# SS_Power-V3_0_a.net
KiCad netlist of a schematic drawn in Altium Designer
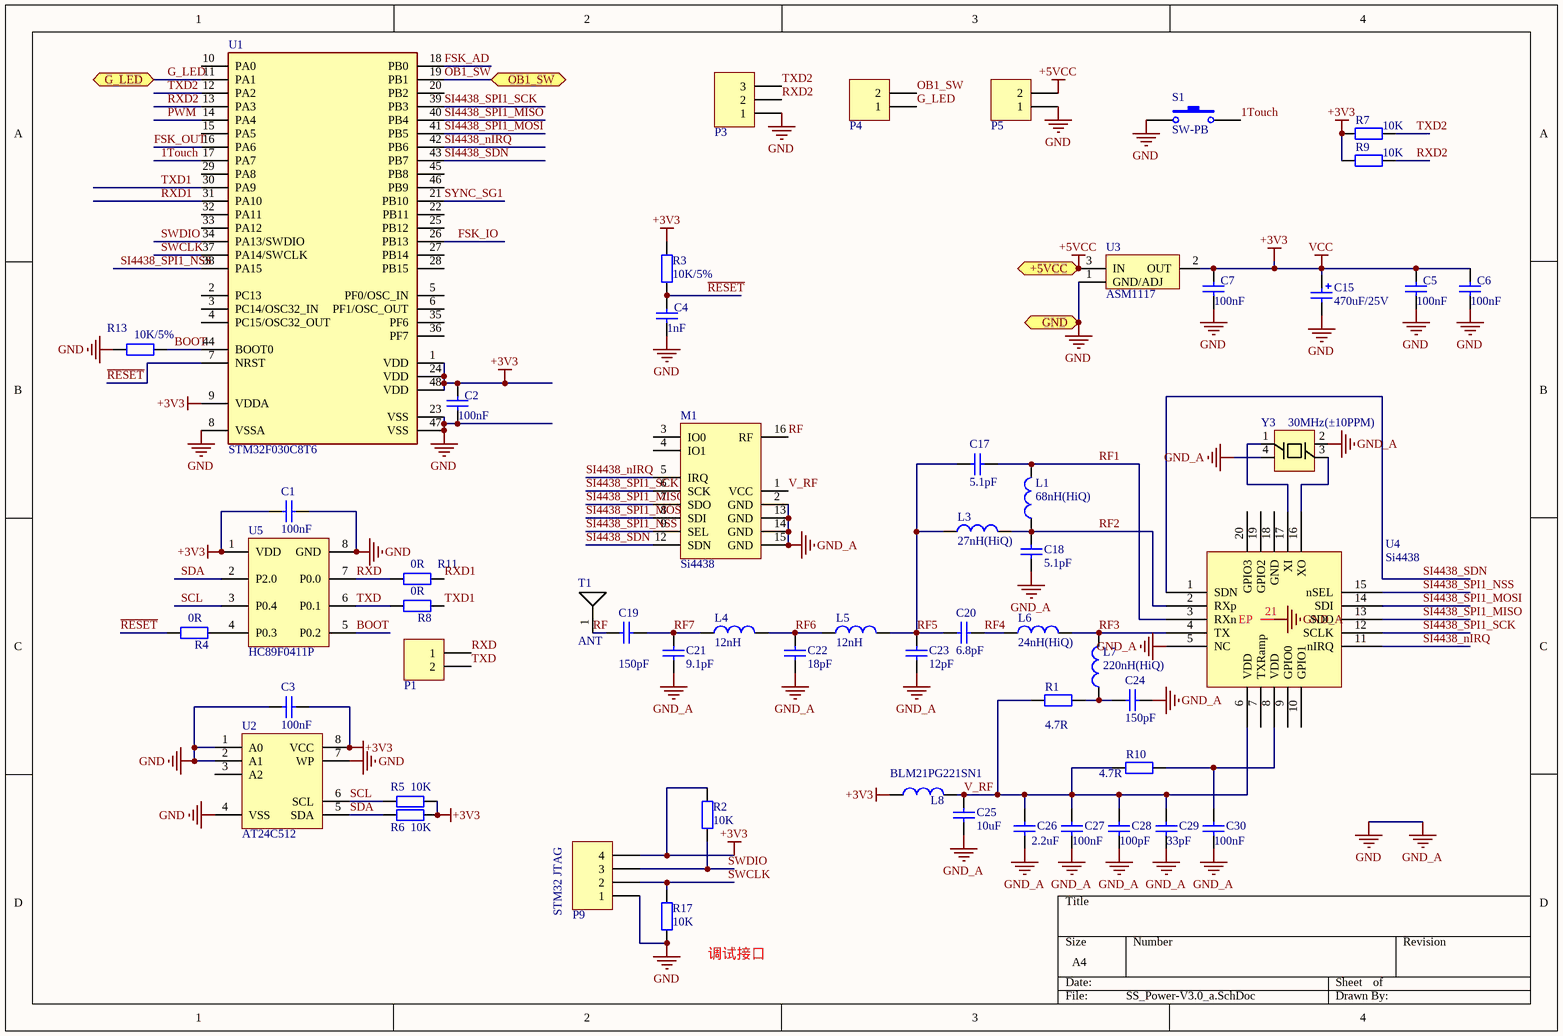
[diagram p0: SS_Power-V3.0_a.SchDoc]

(export (version "E")
  (design (tool "Eeschema 10.0.6"))
  (components
    (comp (ref "C1")
      (value "100nF")
      (footprint "C-RAD-0603")
      (description "无极性电容")
      (fields (field (name "PUBLISHER") "Altium Limited"))
      (libsource (lib "liu_ginny") (part "Cap"))
    )
    (comp (ref "C2")
      (value "100nF")
      (footprint "C-RAD-0603")
      (description "无极性电容")
      (fields (field (name "PUBLISHER") "Altium Limited"))
      (libsource (lib "liu_ginny") (part "Cap"))
    )
    (comp (ref "C3")
      (value "100nF")
      (footprint "C-RAD-0603")
      (description "无极性电容")
      (fields (field (name "PUBLISHER") "Altium Limited"))
      (libsource (lib "liu_ginny") (part "Cap"))
    )
    (comp (ref "C4")
      (value "1nF")
      (footprint "C0402")
      (description "无极性电容")
      (fields (field (name "PUBLISHER") "Altium Limited"))
      (libsource (lib "liu_ginny") (part "Cap"))
    )
    (comp (ref "C5")
      (value "100nF")
      (footprint "C-RAD-0603")
      (description "无极性电容")
      (fields (field (name "PUBLISHER") "Altium Limited"))
      (libsource (lib "liu_ginny") (part "Cap"))
    )
    (comp (ref "C6")
      (value "100nF")
      (footprint "C-RAD-0603")
      (description "无极性电容")
      (fields (field (name "PUBLISHER") "Altium Limited"))
      (libsource (lib "liu_ginny") (part "Cap"))
    )
    (comp (ref "C7")
      (value "100nF")
      (footprint "C-RAD-0603")
      (description "无极性电容")
      (fields (field (name "PUBLISHER") "Altium Limited"))
      (libsource (lib "liu_ginny") (part "Cap"))
    )
    (comp (ref "C15")
      (value "470uF/25V")
      (footprint "C-RB-5/2")
      (description "电解电容")
      (libsource (lib "liu_ginny") (part "CAP3"))
    )
    (comp (ref "C17")
      (value "5.1pF")
      (footprint "C0402")
      (description "无极性电容")
      (fields (field (name "PUBLISHER") "Altium Limited"))
      (libsource (lib "liu_ginny") (part "Cap"))
    )
    (comp (ref "C18")
      (value "5.1pF")
      (footprint "C0402")
      (description "无极性电容")
      (fields (field (name "PUBLISHER") "Altium Limited"))
      (libsource (lib "liu_ginny") (part "Cap"))
    )
    (comp (ref "C19")
      (value "150pF")
      (footprint "C0402")
      (description "无极性电容")
      (fields (field (name "PUBLISHER") "Altium Limited"))
      (libsource (lib "liu_ginny") (part "Cap"))
    )
    (comp (ref "C20")
      (value "6.8pF")
      (footprint "C0402")
      (description "无极性电容")
      (fields (field (name "PUBLISHER") "Altium Limited"))
      (libsource (lib "liu_ginny") (part "Cap"))
    )
    (comp (ref "C21")
      (value "9.1pF")
      (footprint "C0402")
      (description "无极性电容")
      (fields (field (name "PUBLISHER") "Altium Limited"))
      (libsource (lib "liu_ginny") (part "Cap"))
    )
    (comp (ref "C22")
      (value "18pF")
      (footprint "C0402")
      (description "无极性电容")
      (fields (field (name "PUBLISHER") "Altium Limited"))
      (libsource (lib "liu_ginny") (part "Cap"))
    )
    (comp (ref "C23")
      (value "12pF")
      (footprint "C0402")
      (description "无极性电容")
      (fields (field (name "PUBLISHER") "Altium Limited"))
      (libsource (lib "liu_ginny") (part "Cap"))
    )
    (comp (ref "C24")
      (value "150pF")
      (footprint "C0402")
      (description "无极性电容")
      (fields (field (name "PUBLISHER") "Altium Limited"))
      (libsource (lib "liu_ginny") (part "Cap"))
    )
    (comp (ref "C25")
      (value "10uF")
      (footprint "C0603")
      (description "无极性电容")
      (fields (field (name "PUBLISHER") "Altium Limited"))
      (libsource (lib "liu_ginny") (part "Cap"))
    )
    (comp (ref "C26")
      (value "2.2uF")
      (footprint "C0603")
      (description "无极性电容")
      (fields (field (name "PUBLISHER") "Altium Limited"))
      (libsource (lib "liu_ginny") (part "Cap"))
    )
    (comp (ref "C27")
      (value "100nF")
      (footprint "C0402")
      (description "无极性电容")
      (fields (field (name "PUBLISHER") "Altium Limited"))
      (libsource (lib "liu_ginny") (part "Cap"))
    )
    (comp (ref "C28")
      (value "100pF")
      (footprint "C0402")
      (description "无极性电容")
      (fields (field (name "PUBLISHER") "Altium Limited"))
      (libsource (lib "liu_ginny") (part "Cap"))
    )
    (comp (ref "C29")
      (value "33pF")
      (footprint "C0402")
      (description "无极性电容")
      (fields (field (name "PUBLISHER") "Altium Limited"))
      (libsource (lib "liu_ginny") (part "Cap"))
    )
    (comp (ref "C30")
      (value "100nF")
      (footprint "C0402")
      (description "无极性电容")
      (fields (field (name "PUBLISHER") "Altium Limited"))
      (libsource (lib "liu_ginny") (part "Cap"))
    )
    (comp (ref "L1")
      (value "68nH(HiQ)")
      (footprint "0402")
      (description "电感")
      (fields (field (name "PUBLISHER") "Altium Limited"))
      (libsource (lib "liu_ginny") (part "Inductor"))
    )
    (comp (ref "L3")
      (value "27nH(HiQ)")
      (footprint "0402")
      (description "电感")
      (fields (field (name "PUBLISHER") "Altium Limited"))
      (libsource (lib "liu_ginny") (part "Inductor"))
    )
    (comp (ref "L4")
      (value "12nH")
      (footprint "0402")
      (description "电感")
      (fields (field (name "PUBLISHER") "Altium Limited"))
      (libsource (lib "liu_ginny") (part "Inductor"))
    )
    (comp (ref "L5")
      (value "12nH")
      (footprint "0402")
      (description "电感")
      (fields (field (name "PUBLISHER") "Altium Limited"))
      (libsource (lib "liu_ginny") (part "Inductor"))
    )
    (comp (ref "L6")
      (value "24nH(HiQ)")
      (footprint "0402")
      (description "电感")
      (fields (field (name "PUBLISHER") "Altium Limited"))
      (libsource (lib "liu_ginny") (part "Inductor"))
    )
    (comp (ref "L7")
      (value "220nH(HiQ)")
      (footprint "0402")
      (description "电感")
      (fields (field (name "PUBLISHER") "Altium Limited"))
      (libsource (lib "liu_ginny") (part "Inductor"))
    )
    (comp (ref "L8")
      (value "BLM21PG221SN1")
      (footprint "0805-1")
      (description "电感")
      (fields (field (name "PUBLISHER") "Altium Limited"))
      (libsource (lib "liu_ginny") (part "Inductor"))
    )
    (comp (ref "M1")
      (value "Si4438")
      (footprint "HPD01")
      (description "SI4438模块")
      (libsource (lib "liu_ginny") (part "SI4438-HPD07"))
    )
    (comp (ref "P1")
      (value "Header 2")
      (footprint "hdr1.27x2_host")
      (description "接插件")
      (fields (field (name "PUBLISHER") "Altium Limited"))
      (libsource (lib "liu_ginny") (part "Header 2"))
    )
    (comp (ref "P3")
      (value "Header 3")
      (footprint "HDR3X1/1.25")
      (description "接插件")
      (fields (field (name "PUBLISHER") "Altium Limited"))
      (libsource (lib "liu_ginny") (part "Header 3"))
    )
    (comp (ref "P4")
      (value "Header 2")
      (footprint "HDR2X1_2.0")
      (description "接插件")
      (fields (field (name "PUBLISHER") "Altium Limited"))
      (libsource (lib "") (part "Header 2_1"))
    )
    (comp (ref "P5")
      (value "Header 2")
      (footprint "HDR2X1_2.0")
      (description "接插件")
      (fields (field (name "PUBLISHER") "Altium Limited"))
      (libsource (lib "") (part "Header 2_1"))
    )
    (comp (ref "P9")
      (value "Header 4")
      (footprint "HDR4X1/1.25B2M")
      (description "接插件")
      (fields (field (name "PUBLISHER") "Altium Limited"))
      (libsource (lib "liu_ginny") (part "Header 4"))
    )
    (comp (ref "R1")
      (value "4.7R")
      (footprint "R0402")
      (description "电阻")
      (fields (field (name "PUBLISHER") "Altium Limited"))
      (libsource (lib "liu_ginny") (part "Res1"))
    )
    (comp (ref "R2")
      (value "10K")
      (footprint "R0402")
      (description "电阻")
      (fields (field (name "PUBLISHER") "Altium Limited"))
      (libsource (lib "") (part "Res1_1"))
    )
    (comp (ref "R3")
      (value "10K/5%")
      (footprint "R0402")
      (description "电阻")
      (fields (field (name "PUBLISHER") "Altium Limited"))
      (libsource (lib "") (part "Res1_2"))
    )
    (comp (ref "R4")
      (value "0R")
      (footprint "R0402")
      (description "电阻")
      (fields (field (name "PUBLISHER") "Altium Limited"))
      (libsource (lib "liu_ginny") (part "Res1"))
    )
    (comp (ref "R5")
      (value "10K")
      (footprint "R0402")
      (description "电阻")
      (fields (field (name "PUBLISHER") "Altium Limited"))
      (libsource (lib "liu_ginny") (part "Res1"))
    )
    (comp (ref "R6")
      (value "10K")
      (footprint "R0402")
      (description "电阻")
      (fields (field (name "PUBLISHER") "Altium Limited"))
      (libsource (lib "liu_ginny") (part "Res1"))
    )
    (comp (ref "R7")
      (value "10K")
      (footprint "R0402")
      (description "电阻")
      (fields (field (name "PUBLISHER") "Altium Limited"))
      (libsource (lib "liu_ginny") (part "Res1"))
    )
    (comp (ref "R8")
      (value "0R")
      (footprint "R0402")
      (description "电阻")
      (fields (field (name "PUBLISHER") "Altium Limited"))
      (libsource (lib "liu_ginny") (part "Res1"))
    )
    (comp (ref "R9")
      (value "10K")
      (footprint "R0402")
      (description "电阻")
      (fields (field (name "PUBLISHER") "Altium Limited"))
      (libsource (lib "liu_ginny") (part "Res1"))
    )
    (comp (ref "R10")
      (value "4.7R")
      (footprint "R0402")
      (description "电阻")
      (fields (field (name "PUBLISHER") "Altium Limited"))
      (libsource (lib "liu_ginny") (part "Res1"))
    )
    (comp (ref "R11")
      (value "0R")
      (footprint "R0402")
      (description "电阻")
      (fields (field (name "PUBLISHER") "Altium Limited"))
      (libsource (lib "liu_ginny") (part "Res1"))
    )
    (comp (ref "R13")
      (value "10K/5%")
      (footprint "R0402")
      (description "电阻")
      (fields (field (name "PUBLISHER") "Altium Limited"))
      (libsource (lib "liu_ginny") (part "Res1"))
    )
    (comp (ref "R17")
      (value "10K")
      (footprint "R0402")
      (description "电阻")
      (fields (field (name "PUBLISHER") "Altium Limited"))
      (libsource (lib "") (part "Res1_1"))
    )
    (comp (ref "S1")
      (value "SW-PB")
      (footprint "swich_micro")
      (description "微动开关")
      (fields (field (name "PUBLISHER") "Altium Limited"))
      (libsource (lib "liu_ginny") (part "SW-PB"))
    )
    (comp (ref "T1")
      (value "ANT")
      (footprint "ANT470")
      (description "470M弹簧天线")
      (libsource (lib "SCH Library") (part "ANT"))
    )
    (comp (ref "U1")
      (value "STM32F030C8T6")
      (footprint "LQFP48_7X7X05P")
      (description "MCU")
      (libsource (lib "liu_ginny") (part "STM32F030C8T6"))
    )
    (comp (ref "U2")
      (value "AT24C512")
      (footprint "SOIC8_N")
      (description "EEROM存储器")
      (libsource (lib "liu_ginny") (part "AT24C02"))
    )
    (comp (ref "U3") (value "ASM1117") (footprint "SOT-223") (libsource (lib "Core2") (part "ASM1117")))
    (comp (ref "U4")
      (value "Si4438")
      (footprint "QFN20/0.5")
      (description "无线收发器")
      (libsource (lib "liu_ginny") (part "Si4438"))
    )
    (comp (ref "U5")
      (value "HC89F0411P")
      (footprint "SO-8")
      (description "芯圣8脚51单片机")
      (libsource (lib "liu_ginny") (part "HC89F0411P"))
    )
    (comp (ref "Y3")
      (value "30MHz(±10PPM)")
      (footprint "XTAL4/3.2X2.5/S")
      (description "四脚无源")
      (libsource (lib "liu_ginny") (part "XTAL_4"))
    )
  )
  (nets
    (net (code "1") (name "+3V3") (class "Default")
      (node (ref "C1") (pin "2") (pinfunction "2_2") (pintype "passive"))
      (node (ref "C15") (pin "1") (pinfunction "1_1") (pintype "passive"))
      (node (ref "C2") (pin "2") (pinfunction "2_2") (pintype "passive"))
      (node (ref "C3") (pin "1") (pinfunction "1_1") (pintype "passive"))
      (node (ref "C5") (pin "2") (pinfunction "2_2") (pintype "passive"))
      (node (ref "C6") (pin "2") (pinfunction "2_2") (pintype "passive"))
      (node (ref "C7") (pin "2") (pinfunction "2_2") (pintype "passive"))
      (node (ref "L8") (pin "1") (pinfunction "1_1") (pintype "passive"))
      (node (ref "P9") (pin "4") (pinfunction "4_4") (pintype "passive"))
      (node (ref "R2") (pin "1") (pinfunction "1_1") (pintype "passive"))
      (node (ref "R3") (pin "2") (pinfunction "2_2") (pintype "passive"))
      (node (ref "R5") (pin "2") (pinfunction "2_2") (pintype "passive"))
      (node (ref "R6") (pin "2") (pinfunction "2_2") (pintype "passive"))
      (node (ref "R7") (pin "1") (pinfunction "1_1") (pintype "passive"))
      (node (ref "R9") (pin "1") (pinfunction "1_1") (pintype "passive"))
      (node (ref "U1") (pin "1") (pinfunction "VDD_1") (pintype "passive"))
      (node (ref "U1") (pin "24") (pinfunction "VDD_24") (pintype "passive"))
      (node (ref "U1") (pin "48") (pinfunction "VDD_48") (pintype "passive"))
      (node (ref "U1") (pin "9") (pinfunction "VDDA_9") (pintype "passive"))
      (node (ref "U2") (pin "8") (pinfunction "VCC_8") (pintype "passive"))
      (node (ref "U3") (pin "2") (pinfunction "OUT_2") (pintype "passive"))
      (node (ref "U5") (pin "1") (pinfunction "VDD_1") (pintype "passive"))
    )
    (net (code "2") (name "+5VCC") (class "Default")
      (node (ref "P5") (pin "2") (pinfunction "2_2") (pintype "passive"))
      (node (ref "U3") (pin "3") (pinfunction "IN_3") (pintype "passive"))
    )
    (net (code "3") (name "/1Touch") (class "Default")
      (node (ref "S1") (pin "2") (pinfunction "2_2") (pintype "passive"))
      (node (ref "U1") (pin "17") (pinfunction "PA7_17") (pintype "passive"))
    )
    (net (code "4") (name "/BOOT") (class "Default")
      (node (ref "R13") (pin "2") (pinfunction "2_2") (pintype "passive"))
      (node (ref "U1") (pin "44") (pinfunction "BOOT0_44") (pintype "passive"))
      (node (ref "U5") (pin "5") (pinfunction "P0.2_5") (pintype "passive"))
    )
    (net (code "5") (name "/FSK_AD") (class "Default")
      (node (ref "U1") (pin "18") (pinfunction "PB0_18") (pintype "passive"))
    )
    (net (code "6") (name "/FSK_IO") (class "Default")
      (node (ref "U1") (pin "26") (pinfunction "PB13_26") (pintype "passive"))
    )
    (net (code "7") (name "/FSK_OUT") (class "Default")
      (node (ref "U1") (pin "16") (pinfunction "PA6_16") (pintype "passive"))
    )
    (net (code "8") (name "/G_LED") (class "Default")
      (node (ref "P4") (pin "1") (pinfunction "1_1") (pintype "passive"))
      (node (ref "U1") (pin "11") (pinfunction "PA1_11") (pintype "passive"))
    )
    (net (code "9") (name "/OB1_SW") (class "Default")
      (node (ref "P4") (pin "2") (pinfunction "2_2") (pintype "passive"))
      (node (ref "U1") (pin "19") (pinfunction "PB1_19") (pintype "passive"))
    )
    (net (code "10") (name "/PWM") (class "Default")
      (node (ref "U1") (pin "14") (pinfunction "PA4_14") (pintype "passive"))
    )
    (net (code "11") (name "/RF") (class "Default")
      (node (ref "C19") (pin "1") (pinfunction "1_1") (pintype "passive"))
      (node (ref "M1") (pin "16") (pinfunction "RF_16") (pintype "passive"))
      (node (ref "T1") (pin "1") (pinfunction "1_1") (pintype "passive"))
    )
    (net (code "12") (name "/RF1") (class "Default")
      (node (ref "C17") (pin "2") (pinfunction "2_2") (pintype "passive"))
      (node (ref "L1") (pin "2") (pinfunction "2_2") (pintype "passive"))
      (node (ref "U4") (pin "3") (pinfunction "RXn_3") (pintype "passive"))
    )
    (net (code "13") (name "/RF2") (class "Default")
      (node (ref "C18") (pin "1") (pinfunction "1_1") (pintype "passive"))
      (node (ref "L1") (pin "1") (pinfunction "1_1") (pintype "passive"))
      (node (ref "L3") (pin "2") (pinfunction "2_2") (pintype "passive"))
      (node (ref "U4") (pin "2") (pinfunction "RXp_2") (pintype "passive"))
    )
    (net (code "14") (name "/RF3") (class "Default")
      (node (ref "L6") (pin "2") (pinfunction "2_2") (pintype "passive"))
      (node (ref "L7") (pin "2") (pinfunction "2_2") (pintype "passive"))
      (node (ref "U4") (pin "4") (pinfunction "TX_4") (pintype "passive"))
    )
    (net (code "15") (name "/RF4") (class "Default")
      (node (ref "C20") (pin "1") (pinfunction "1_1") (pintype "passive"))
      (node (ref "L6") (pin "1") (pinfunction "1_1") (pintype "passive"))
    )
    (net (code "16") (name "/RF5") (class "Default")
      (node (ref "C17") (pin "1") (pinfunction "1_1") (pintype "passive"))
      (node (ref "C20") (pin "2") (pinfunction "2_2") (pintype "passive"))
      (node (ref "C23") (pin "2") (pinfunction "2_2") (pintype "passive"))
      (node (ref "L3") (pin "1") (pinfunction "1_1") (pintype "passive"))
      (node (ref "L5") (pin "2") (pinfunction "2_2") (pintype "passive"))
    )
    (net (code "17") (name "/RF6") (class "Default")
      (node (ref "C22") (pin "2") (pinfunction "2_2") (pintype "passive"))
      (node (ref "L4") (pin "2") (pinfunction "2_2") (pintype "passive"))
      (node (ref "L5") (pin "1") (pinfunction "1_1") (pintype "passive"))
    )
    (net (code "18") (name "/RF7") (class "Default")
      (node (ref "C19") (pin "2") (pinfunction "2_2") (pintype "passive"))
      (node (ref "C21") (pin "2") (pinfunction "2_2") (pintype "passive"))
      (node (ref "L4") (pin "1") (pinfunction "1_1") (pintype "passive"))
    )
    (net (code "19") (name "/RXD") (class "Default")
      (node (ref "P1") (pin "1") (pinfunction "1_1") (pintype "passive"))
      (node (ref "R11") (pin "1") (pinfunction "1_1") (pintype "passive"))
      (node (ref "U5") (pin "7") (pinfunction "P0.0_7") (pintype "passive"))
    )
    (net (code "20") (name "/RXD1") (class "Default")
      (node (ref "R11") (pin "2") (pinfunction "2_2") (pintype "passive"))
      (node (ref "U1") (pin "31") (pinfunction "PA10_31") (pintype "passive"))
    )
    (net (code "21") (name "/RXD2") (class "Default")
      (node (ref "P3") (pin "2") (pinfunction "2_2") (pintype "passive"))
      (node (ref "R9") (pin "2") (pinfunction "2_2") (pintype "passive"))
      (node (ref "U1") (pin "13") (pinfunction "PA3_13") (pintype "passive"))
    )
    (net (code "22") (name "/SCL") (class "Default")
      (node (ref "R5") (pin "1") (pinfunction "1_1") (pintype "passive"))
      (node (ref "U2") (pin "6") (pinfunction "SCL_6") (pintype "passive"))
      (node (ref "U5") (pin "3") (pinfunction "P0.4_3") (pintype "passive"))
    )
    (net (code "23") (name "/SDA") (class "Default")
      (node (ref "R6") (pin "1") (pinfunction "1_1") (pintype "passive"))
      (node (ref "U2") (pin "5") (pinfunction "SDA_5") (pintype "passive"))
      (node (ref "U5") (pin "2") (pinfunction "P2.0_2") (pintype "passive"))
    )
    (net (code "24") (name "/SI4438_SDN") (class "Default")
      (node (ref "M1") (pin "12") (pinfunction "SDN_12") (pintype "passive"))
      (node (ref "U1") (pin "43") (pinfunction "PB7_43") (pintype "passive"))
      (node (ref "U4") (pin "1") (pinfunction "SDN_1") (pintype "passive"))
    )
    (net (code "25") (name "/SI4438_SPI1_MISO") (class "Default")
      (node (ref "M1") (pin "7") (pinfunction "SDO_7") (pintype "passive"))
      (node (ref "U1") (pin "40") (pinfunction "PB4_40") (pintype "passive"))
      (node (ref "U4") (pin "13") (pinfunction "SDO_13") (pintype "passive"))
    )
    (net (code "26") (name "/SI4438_SPI1_MOSI") (class "Default")
      (node (ref "M1") (pin "8") (pinfunction "SDI_8") (pintype "passive"))
      (node (ref "U1") (pin "41") (pinfunction "PB5_41") (pintype "passive"))
      (node (ref "U4") (pin "14") (pinfunction "SDI_14") (pintype "passive"))
    )
    (net (code "27") (name "/SI4438_SPI1_NSS") (class "Default")
      (node (ref "M1") (pin "9") (pinfunction "SEL_9") (pintype "passive"))
      (node (ref "U1") (pin "38") (pinfunction "PA15_38") (pintype "passive"))
      (node (ref "U4") (pin "15") (pinfunction "nSEL_15") (pintype "passive"))
    )
    (net (code "28") (name "/SI4438_SPI1_SCK") (class "Default")
      (node (ref "M1") (pin "6") (pinfunction "SCK_6") (pintype "passive"))
      (node (ref "U1") (pin "39") (pinfunction "PB3_39") (pintype "passive"))
      (node (ref "U4") (pin "12") (pinfunction "SCLK_12") (pintype "passive"))
    )
    (net (code "29") (name "/SI4438_nIRQ") (class "Default")
      (node (ref "M1") (pin "5") (pinfunction "IRQ_5") (pintype "passive"))
      (node (ref "U1") (pin "42") (pinfunction "PB6_42") (pintype "passive"))
      (node (ref "U4") (pin "11") (pinfunction "nIRQ_11") (pintype "passive"))
    )
    (net (code "30") (name "/SWCLK") (class "Default")
      (node (ref "P9") (pin "2") (pinfunction "2_2") (pintype "passive"))
      (node (ref "R17") (pin "1") (pinfunction "1_1") (pintype "passive"))
      (node (ref "U1") (pin "37") (pinfunction "PA14/SWCLK_37") (pintype "passive"))
    )
    (net (code "31") (name "/SWDIO") (class "Default")
      (node (ref "P9") (pin "3") (pinfunction "3_3") (pintype "passive"))
      (node (ref "R2") (pin "2") (pinfunction "2_2") (pintype "passive"))
      (node (ref "U1") (pin "34") (pinfunction "PA13/SWDIO_34") (pintype "passive"))
    )
    (net (code "32") (name "/SYNC_SG1") (class "Default")
      (node (ref "U1") (pin "21") (pinfunction "PB10_21") (pintype "passive"))
    )
    (net (code "33") (name "/TXD") (class "Default")
      (node (ref "P1") (pin "2") (pinfunction "2_2") (pintype "passive"))
      (node (ref "R8") (pin "1") (pinfunction "1_1") (pintype "passive"))
      (node (ref "U5") (pin "6") (pinfunction "P0.1_6") (pintype "passive"))
    )
    (net (code "34") (name "/TXD1") (class "Default")
      (node (ref "R8") (pin "2") (pinfunction "2_2") (pintype "passive"))
      (node (ref "U1") (pin "30") (pinfunction "PA9_30") (pintype "passive"))
    )
    (net (code "35") (name "/TXD2") (class "Default")
      (node (ref "P3") (pin "3") (pinfunction "3_3") (pintype "passive"))
      (node (ref "R7") (pin "2") (pinfunction "2_2") (pintype "passive"))
      (node (ref "U1") (pin "12") (pinfunction "PA2_12") (pintype "passive"))
    )
    (net (code "36") (name "/V_RF") (class "Default")
      (node (ref "C25") (pin "2") (pinfunction "2_2") (pintype "passive"))
      (node (ref "C26") (pin "2") (pinfunction "2_2") (pintype "passive"))
      (node (ref "C27") (pin "2") (pinfunction "2_2") (pintype "passive"))
      (node (ref "C28") (pin "2") (pinfunction "2_2") (pintype "passive"))
      (node (ref "C29") (pin "2") (pinfunction "2_2") (pintype "passive"))
      (node (ref "L8") (pin "2") (pinfunction "2_2") (pintype "passive"))
      (node (ref "M1") (pin "1") (pinfunction "VCC_1") (pintype "passive"))
      (node (ref "R1") (pin "1") (pinfunction "1_1") (pintype "passive"))
      (node (ref "R10") (pin "1") (pinfunction "1_1") (pintype "passive"))
      (node (ref "U4") (pin "6") (pinfunction "VDD_6") (pintype "passive"))
    )
    (net (code "37") (name "/~{RESET}") (class "Default")
      (node (ref "C4") (pin "2") (pinfunction "2_2") (pintype "passive"))
      (node (ref "R3") (pin "1") (pinfunction "1_1") (pintype "passive"))
      (node (ref "R4") (pin "1") (pinfunction "1_1") (pintype "passive"))
      (node (ref "U1") (pin "7") (pinfunction "NRST_7") (pintype "passive"))
    )
    (net (code "38") (name "GND") (class "Default")
      (node (ref "C1") (pin "1") (pinfunction "1_1") (pintype "passive"))
      (node (ref "C15") (pin "2") (pinfunction "2_2") (pintype "passive"))
      (node (ref "C18") (pin "2") (pinfunction "2_2") (pintype "passive"))
      (node (ref "C2") (pin "1") (pinfunction "1_1") (pintype "passive"))
      (node (ref "C21") (pin "1") (pinfunction "1_1") (pintype "passive"))
      (node (ref "C22") (pin "1") (pinfunction "1_1") (pintype "passive"))
      (node (ref "C23") (pin "1") (pinfunction "1_1") (pintype "passive"))
      (node (ref "C24") (pin "1") (pinfunction "1_1") (pintype "passive"))
      (node (ref "C25") (pin "1") (pinfunction "1_1") (pintype "passive"))
      (node (ref "C26") (pin "1") (pinfunction "1_1") (pintype "passive"))
      (node (ref "C27") (pin "1") (pinfunction "1_1") (pintype "passive"))
      (node (ref "C28") (pin "1") (pinfunction "1_1") (pintype "passive"))
      (node (ref "C29") (pin "1") (pinfunction "1_1") (pintype "passive"))
      (node (ref "C3") (pin "2") (pinfunction "2_2") (pintype "passive"))
      (node (ref "C30") (pin "1") (pinfunction "1_1") (pintype "passive"))
      (node (ref "C4") (pin "1") (pinfunction "1_1") (pintype "passive"))
      (node (ref "C5") (pin "1") (pinfunction "1_1") (pintype "passive"))
      (node (ref "C6") (pin "1") (pinfunction "1_1") (pintype "passive"))
      (node (ref "C7") (pin "1") (pinfunction "1_1") (pintype "passive"))
      (node (ref "M1") (pin "13") (pinfunction "GND_13") (pintype "passive"))
      (node (ref "M1") (pin "14") (pinfunction "GND_14") (pintype "passive"))
      (node (ref "M1") (pin "15") (pinfunction "GND_15") (pintype "passive"))
      (node (ref "M1") (pin "2") (pinfunction "GND_2") (pintype "passive"))
      (node (ref "P3") (pin "1") (pinfunction "1_1") (pintype "passive"))
      (node (ref "P5") (pin "1") (pinfunction "1_1") (pintype "passive"))
      (node (ref "P9") (pin "1") (pinfunction "1_1") (pintype "passive"))
      (node (ref "R13") (pin "1") (pinfunction "1_1") (pintype "passive"))
      (node (ref "R17") (pin "2") (pinfunction "2_2") (pintype "passive"))
      (node (ref "S1") (pin "1") (pinfunction "1_1") (pintype "passive"))
      (node (ref "U1") (pin "23") (pinfunction "VSS_23") (pintype "passive"))
      (node (ref "U1") (pin "47") (pinfunction "VSS_47") (pintype "passive"))
      (node (ref "U1") (pin "8") (pinfunction "VSSA_8") (pintype "passive"))
      (node (ref "U2") (pin "1") (pinfunction "A0_1") (pintype "passive"))
      (node (ref "U2") (pin "2") (pinfunction "A1_2") (pintype "passive"))
      (node (ref "U2") (pin "4") (pinfunction "VSS_4") (pintype "passive"))
      (node (ref "U2") (pin "7") (pinfunction "WP_7") (pintype "passive"))
      (node (ref "U3") (pin "1") (pinfunction "GND/ADJ_1") (pintype "passive"))
      (node (ref "U4") (pin "21") (pinfunction "EP_21") (pintype "passive"))
      (node (ref "U4") (pin "5") (pinfunction "NC_5") (pintype "passive"))
      (node (ref "U5") (pin "8") (pinfunction "GND_8") (pintype "passive"))
      (node (ref "Y3") (pin "2") (pinfunction "50_2") (pintype "passive"))
      (node (ref "Y3") (pin "4") (pinfunction "51_4") (pintype "passive"))
    )
    (net (code "39") (name "Net-(C24-Pad2)") (class "Default")
      (node (ref "C24") (pin "2") (pinfunction "2_2") (pintype "passive"))
      (node (ref "L7") (pin "1") (pinfunction "1_1") (pintype "passive"))
      (node (ref "R1") (pin "2") (pinfunction "2_2") (pintype "passive"))
    )
    (net (code "40") (name "Net-(C30-Pad2)") (class "Default")
      (node (ref "C30") (pin "2") (pinfunction "2_2") (pintype "passive"))
      (node (ref "R10") (pin "2") (pinfunction "2_2") (pintype "passive"))
      (node (ref "U4") (pin "8") (pinfunction "VDD_8") (pintype "passive"))
    )
    (net (code "41") (name "Net-(U4-XI)") (class "Default")
      (node (ref "U4") (pin "17") (pinfunction "XI_17") (pintype "passive"))
      (node (ref "Y3") (pin "1") (pinfunction "52_1") (pintype "passive"))
    )
    (net (code "42") (name "Net-(U4-XO)") (class "Default")
      (node (ref "U4") (pin "16") (pinfunction "XO_16") (pintype "passive"))
      (node (ref "Y3") (pin "3") (pinfunction "49_3") (pintype "passive"))
    )
    (net (code "43") (name "Net-(U5-P0.3)") (class "Default")
      (node (ref "R4") (pin "2") (pinfunction "2_2") (pintype "passive"))
      (node (ref "U5") (pin "4") (pinfunction "P0.3_4") (pintype "passive"))
    )
    (net (code "44") (name "unconnected-(M1-IO0-Pad3)") (class "Default")
      (node (ref "M1") (pin "3") (pinfunction "IO0_3") (pintype "passive"))
    )
    (net (code "45") (name "unconnected-(M1-IO1-Pad4)") (class "Default")
      (node (ref "M1") (pin "4") (pinfunction "IO1_4") (pintype "passive"))
    )
    (net (code "46") (name "unconnected-(U1-PA0-Pad10)") (class "Default")
      (node (ref "U1") (pin "10") (pinfunction "PA0_10") (pintype "passive"))
    )
    (net (code "47") (name "unconnected-(U1-PA5-Pad15)") (class "Default")
      (node (ref "U1") (pin "15") (pinfunction "PA5_15") (pintype "passive"))
    )
    (net (code "48") (name "unconnected-(U1-PA8-Pad29)") (class "Default")
      (node (ref "U1") (pin "29") (pinfunction "PA8_29") (pintype "passive"))
    )
    (net (code "49") (name "unconnected-(U1-PA11-Pad32)") (class "Default")
      (node (ref "U1") (pin "32") (pinfunction "PA11_32") (pintype "passive"))
    )
    (net (code "50") (name "unconnected-(U1-PA12-Pad33)") (class "Default")
      (node (ref "U1") (pin "33") (pinfunction "PA12_33") (pintype "passive"))
    )
    (net (code "51") (name "unconnected-(U1-PB2-Pad20)") (class "Default")
      (node (ref "U1") (pin "20") (pinfunction "PB2_20") (pintype "passive"))
    )
    (net (code "52") (name "unconnected-(U1-PB8-Pad45)") (class "Default")
      (node (ref "U1") (pin "45") (pinfunction "PB8_45") (pintype "passive"))
    )
    (net (code "53") (name "unconnected-(U1-PB9-Pad46)") (class "Default")
      (node (ref "U1") (pin "46") (pinfunction "PB9_46") (pintype "passive"))
    )
    (net (code "54") (name "unconnected-(U1-PB11-Pad22)") (class "Default")
      (node (ref "U1") (pin "22") (pinfunction "PB11_22") (pintype "passive"))
    )
    (net (code "55") (name "unconnected-(U1-PB12-Pad25)") (class "Default")
      (node (ref "U1") (pin "25") (pinfunction "PB12_25") (pintype "passive"))
    )
    (net (code "56") (name "unconnected-(U1-PB14-Pad27)") (class "Default")
      (node (ref "U1") (pin "27") (pinfunction "PB14_27") (pintype "passive"))
    )
    (net (code "57") (name "unconnected-(U1-PB15-Pad28)") (class "Default")
      (node (ref "U1") (pin "28") (pinfunction "PB15_28") (pintype "passive"))
    )
    (net (code "58") (name "unconnected-(U1-PC13-Pad2)") (class "Default")
      (node (ref "U1") (pin "2") (pinfunction "PC13_2") (pintype "passive"))
    )
    (net (code "59") (name "unconnected-(U1-PC14{slash}OSC32_IN-Pad3)") (class "Default")
      (node (ref "U1") (pin "3") (pinfunction "PC14/OSC32_IN_3") (pintype "passive"))
    )
    (net (code "60") (name "unconnected-(U1-PC15{slash}OSC32_OUT-Pad4)") (class "Default")
      (node (ref "U1") (pin "4") (pinfunction "PC15/OSC32_OUT_4") (pintype "passive"))
    )
    (net (code "61") (name "unconnected-(U1-PF0{slash}OSC_IN-Pad5)") (class "Default")
      (node (ref "U1") (pin "5") (pinfunction "PF0/OSC_IN_5") (pintype "passive"))
    )
    (net (code "62") (name "unconnected-(U1-PF1{slash}OSC_OUT-Pad6)") (class "Default")
      (node (ref "U1") (pin "6") (pinfunction "PF1/OSC_OUT_6") (pintype "passive"))
    )
    (net (code "63") (name "unconnected-(U1-PF6-Pad35)") (class "Default")
      (node (ref "U1") (pin "35") (pinfunction "PF6_35") (pintype "passive"))
    )
    (net (code "64") (name "unconnected-(U1-PF7-Pad36)") (class "Default")
      (node (ref "U1") (pin "36") (pinfunction "PF7_36") (pintype "passive"))
    )
    (net (code "65") (name "unconnected-(U2-A2-Pad3)") (class "Default")
      (node (ref "U2") (pin "3") (pinfunction "A2_3") (pintype "passive"))
    )
    (net (code "66") (name "unconnected-(U4-GND-Pad18)") (class "Default")
      (node (ref "U4") (pin "18") (pinfunction "GND_18") (pintype "passive"))
    )
    (net (code "67") (name "unconnected-(U4-GPIO0-Pad9)") (class "Default")
      (node (ref "U4") (pin "9") (pinfunction "GPIO0_9") (pintype "passive"))
    )
    (net (code "68") (name "unconnected-(U4-GPIO1-Pad10)") (class "Default")
      (node (ref "U4") (pin "10") (pinfunction "GPIO1_10") (pintype "passive"))
    )
    (net (code "69") (name "unconnected-(U4-GPIO2-Pad19)") (class "Default")
      (node (ref "U4") (pin "19") (pinfunction "GPIO2_19") (pintype "passive"))
    )
    (net (code "70") (name "unconnected-(U4-GPIO3-Pad20)") (class "Default")
      (node (ref "U4") (pin "20") (pinfunction "GPIO3_20") (pintype "passive"))
    )
    (net (code "71") (name "unconnected-(U4-TXRamp-Pad7)") (class "Default")
      (node (ref "U4") (pin "7") (pinfunction "TXRamp_7") (pintype "passive"))
    )
  )
)
